# USB_Downloader.net
KiCad netlist of a schematic drawn in Altium Designer
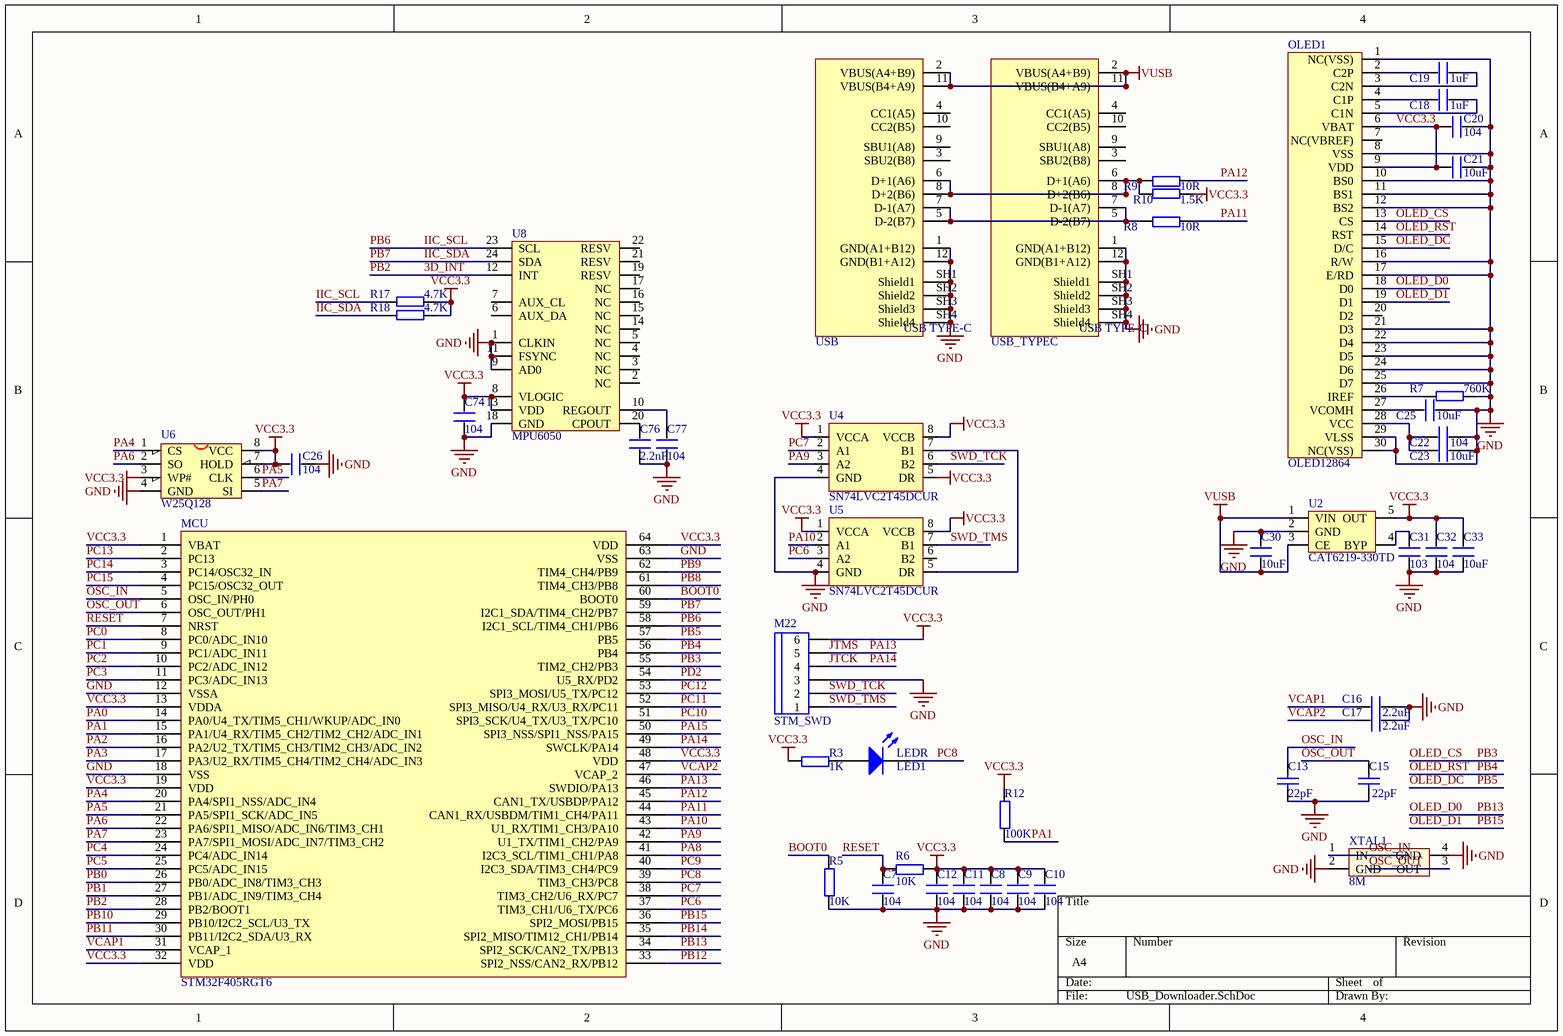
[diagram p0: USB_Downloader.SchDoc]

(export (version "E")
  (design (tool "Eeschema 10.0.6"))
  (components
    (comp (ref "C7")
      (value "104")
      (footprint "C 0603_L")
      (libsource (lib "WarShip V3 STM32103封装库") (part "C"))
    )
    (comp (ref "C8")
      (value "104")
      (footprint "C 0603_L")
      (libsource (lib "WarShip V3 STM32103封装库") (part "C"))
    )
    (comp (ref "C9")
      (value "104")
      (footprint "C 0603_L")
      (libsource (lib "WarShip V3 STM32103封装库") (part "C"))
    )
    (comp (ref "C10")
      (value "104")
      (footprint "C 0603_L")
      (libsource (lib "WarShip V3 STM32103封装库") (part "C"))
    )
    (comp (ref "C11")
      (value "104")
      (footprint "C 0603_L")
      (libsource (lib "WarShip V3 STM32103封装库") (part "C"))
    )
    (comp (ref "C12")
      (value "104")
      (footprint "C 0603_L")
      (libsource (lib "WarShip V3 STM32103封装库") (part "C"))
    )
    (comp (ref "C13") (value "22pF") (footprint "C 0603_L") (libsource (lib "L476") (part "CAP")))
    (comp (ref "C15") (value "22pF") (footprint "C 0603_L") (libsource (lib "L476") (part "CAP")))
    (comp (ref "C16")
      (value "2.2uF")
      (footprint "C 0603_L")
      (libsource (lib "WarShip V3 STM32103封装库") (part "C"))
    )
    (comp (ref "C17")
      (value "2.2uF")
      (footprint "C 0603_L")
      (libsource (lib "WarShip V3 STM32103封装库") (part "C"))
    )
    (comp (ref "C18")
      (value "1uF")
      (footprint "C 0603_L")
      (libsource (lib "WarShip V3 STM32103封装库") (part "C"))
    )
    (comp (ref "C19")
      (value "1uF")
      (footprint "C 0603_L")
      (libsource (lib "WarShip V3 STM32103封装库") (part "C"))
    )
    (comp (ref "C20")
      (value "104")
      (footprint "C 0603_L")
      (libsource (lib "WarShip V3 STM32103封装库") (part "C"))
    )
    (comp (ref "C21")
      (value "10uF")
      (footprint "C 0603_L")
      (libsource (lib "WarShip V3 STM32103封装库") (part "C"))
    )
    (comp (ref "C22")
      (value "104")
      (footprint "C 0603_L")
      (libsource (lib "WarShip V3 STM32103封装库") (part "C"))
    )
    (comp (ref "C23")
      (value "10uF")
      (footprint "C 0603_L")
      (libsource (lib "WarShip V3 STM32103封装库") (part "C"))
    )
    (comp (ref "C25")
      (value "10uF")
      (footprint "C 0603_L")
      (libsource (lib "WarShip V3 STM32103封装库") (part "C"))
    )
    (comp (ref "C26")
      (value "104")
      (footprint "C 0603_L")
      (libsource (lib "WarShip V3 STM32103封装库") (part "C"))
    )
    (comp (ref "C30")
      (value "10uF")
      (footprint "C 0603_L")
      (libsource (lib "WarShip V3 STM32103封装库") (part "C"))
    )
    (comp (ref "C31")
      (value "103")
      (footprint "C 0603_L")
      (libsource (lib "WarShip V3 STM32103封装库") (part "C"))
    )
    (comp (ref "C32")
      (value "104")
      (footprint "C 0603_L")
      (libsource (lib "WarShip V3 STM32103封装库") (part "C"))
    )
    (comp (ref "C33")
      (value "10uF")
      (footprint "C 0603_L")
      (libsource (lib "WarShip V3 STM32103封装库") (part "C"))
    )
    (comp (ref "C74") (value "104") (footprint "C 0603_L") (libsource (lib "MYCOMLIB") (part "C")))
    (comp (ref "C76") (value "2.2nF") (footprint "C 0603_L") (libsource (lib "MYCOMLIB") (part "C")))
    (comp (ref "C77") (value "104") (footprint "C 0603_L") (libsource (lib "MYCOMLIB") (part "C")))
    (comp (ref "LEDR")
      (value "LED1")
      (footprint "LED 0805B")
      (description "Typical RED, GREEN, YELLOW, AMBER GaAs LED")
      (fields (field (name "PUBLISHER") "Altium Limited"))
      (libsource (lib "阿波罗STM32F4&F7底板封装库") (part "LED2"))
    )
    (comp (ref "M22") (value "STM_SWD") (footprint "SH1.0-6P") (libsource (lib "MiniFly ") (part "HEAD6")))
    (comp (ref "MCU")
      (value "STM32F405RGT6")
      (footprint "LQFP64 10X10_L")
      (description "Flaah:256/RAM:48/IO:51")
      (libsource (lib "ATKF405 V1.1") (part "STM32F405RGT6"))
    )
    (comp (ref "OLED1")
      (value "OLED12864")
      (footprint "OLED_0.96")
      (libsource (lib "OLED模块封装库") (part "OLED12864"))
    )
    (comp (ref "R3")
      (value "1K")
      (footprint "R 0603_L")
      (libsource (lib "WarShip V3 STM32103封装库") (part "R"))
    )
    (comp (ref "R5")
      (value "10K")
      (footprint "R 0603_L")
      (libsource (lib "WarShip V3 STM32103封装库") (part "R"))
    )
    (comp (ref "R6")
      (value "10K")
      (footprint "R 0603_L")
      (libsource (lib "WarShip V3 STM32103封装库") (part "R"))
    )
    (comp (ref "R7")
      (value "760K")
      (footprint "R 0603_L")
      (libsource (lib "WarShip V3 STM32103封装库") (part "R"))
    )
    (comp (ref "R8")
      (value "10R")
      (footprint "R 0603_L")
      (libsource (lib "WarShip V3 STM32103封装库") (part "R"))
    )
    (comp (ref "R9")
      (value "10R")
      (footprint "R 0603_L")
      (libsource (lib "WarShip V3 STM32103封装库") (part "R"))
    )
    (comp (ref "R10")
      (value "1.5K")
      (footprint "R 0603_L")
      (libsource (lib "WarShip V3 STM32103封装库") (part "R"))
    )
    (comp (ref "R12")
      (value "100K")
      (footprint "R 0603_L")
      (libsource (lib "WarShip V3 STM32103封装库") (part "R"))
    )
    (comp (ref "R17")
      (value "4.7K")
      (footprint "R 0603_L")
      (libsource (lib "WarShip V3 STM32103封装库") (part "R"))
    )
    (comp (ref "R18")
      (value "4.7K")
      (footprint "R 0603_L")
      (libsource (lib "WarShip V3 STM32103封装库") (part "R"))
    )
    (comp (ref "U2")
      (value "CAT6219-330TD")
      (footprint "SOT23-5L")
      (description "3.3V 500mA LDO")
      (libsource (lib "STM32H743核心板封装库") (part "CAT6219-330TD"))
    )
    (comp (ref "U4")
      (value "SN74LVC2T45DCUR")
      (footprint "SN74LVC2T45DCUR")
      (description "双位双电源总线收发器")
      (libsource (lib "LovelessingSch") (part "SN74LVC2T45DCUR"))
    )
    (comp (ref "U5")
      (value "SN74LVC2T45DCUR")
      (footprint "SN74LVC2T45DCUR")
      (description "双位双电源总线收发器")
      (libsource (lib "LovelessingSch") (part "SN74LVC2T45DCUR"))
    )
    (comp (ref "U6")
      (value "W25Q128")
      (footprint "SOP8W_L")
      (description "W25X16;SST25VF016;MX25L1605")
      (libsource (lib "WarShip V3 STM32103封装库") (part "W25X16"))
    )
    (comp (ref "U8")
      (value "MPU6050")
      (footprint "QFN24 4x4_N")
      (description "9轴运动处理传感器")
      (libsource (lib "ALIENTEK_COMPONENT") (part "MPU6050"))
    )
    (comp (ref "USB")
      (value "USB TypeC")
      (footprint "USB Type-C")
      (description "12P TypeC 母座")
      (libsource (lib "ESP32_Weather") (part "USB Type-C"))
    )
    (comp (ref "USB_TYPEC")
      (value "USB TypeC")
      (footprint "USB Type-C")
      (description "12P TypeC 母座")
      (libsource (lib "ESP32_Weather") (part "USB Type-C"))
    )
    (comp (ref "XTAL1")
      (value "8M")
      (footprint "XTAL3225   无源")
      (description "无源贴片晶振")
      (libsource (lib "REMOTOR") (part "XTAL-无源贴片"))
    )
  )
  (nets
    (net (code "1") (name "/3D_INT") (class "Default")
      (node (ref "MCU") (pin "28") (pinfunction "PB2/BOOT1_28") (pintype "passive"))
      (node (ref "U8") (pin "12") (pinfunction "INT_12") (pintype "passive"))
    )
    (net (code "2") (name "/BOOT0") (class "Default")
      (node (ref "MCU") (pin "60") (pinfunction "BOOT0_60") (pintype "passive"))
      (node (ref "R5") (pin "2") (pintype "passive"))
    )
    (net (code "3") (name "/IIC_SCL") (class "Default")
      (node (ref "MCU") (pin "58") (pinfunction "I2C1_SCL/TIM4_CH1/PB6_58") (pintype "passive"))
      (node (ref "R17") (pin "2") (pintype "passive"))
      (node (ref "U8") (pin "23") (pinfunction "SCL_23") (pintype "passive"))
    )
    (net (code "4") (name "/IIC_SDA") (class "Default")
      (node (ref "MCU") (pin "59") (pinfunction "I2C1_SDA/TIM4_CH2/PB7_59") (pintype "passive"))
      (node (ref "R18") (pin "2") (pintype "passive"))
      (node (ref "U8") (pin "24") (pinfunction "SDA_24") (pintype "passive"))
    )
    (net (code "5") (name "/JTCK") (class "Default")
      (node (ref "M22") (pin "4") (pinfunction "4_4") (pintype "passive"))
      (node (ref "MCU") (pin "49") (pinfunction "SWCLK/PA14_49") (pintype "passive"))
    )
    (net (code "6") (name "/JTMS") (class "Default")
      (node (ref "M22") (pin "5") (pinfunction "5_5") (pintype "passive"))
      (node (ref "MCU") (pin "46") (pinfunction "SWDIO/PA13_46") (pintype "passive"))
    )
    (net (code "7") (name "/OLED_CS") (class "Default")
      (node (ref "MCU") (pin "55") (pinfunction "TIM2_CH2/PB3_55") (pintype "passive"))
      (node (ref "OLED1") (pin "13") (pinfunction "CS_13") (pintype "passive"))
    )
    (net (code "8") (name "/OLED_D0") (class "Default")
      (node (ref "MCU") (pin "34") (pinfunction "SPI2_SCK/CAN2_TX/PB13_34") (pintype "passive"))
      (node (ref "OLED1") (pin "18") (pinfunction "D0_18") (pintype "passive"))
    )
    (net (code "9") (name "/OLED_D1") (class "Default")
      (node (ref "MCU") (pin "36") (pinfunction "SPI2_MOSI/PB15_36") (pintype "passive"))
      (node (ref "OLED1") (pin "19") (pinfunction "D1_19") (pintype "passive"))
    )
    (net (code "10") (name "/OLED_DC") (class "Default")
      (node (ref "MCU") (pin "57") (pinfunction "PB5_57") (pintype "passive"))
      (node (ref "OLED1") (pin "15") (pinfunction "D/C_15") (pintype "passive"))
    )
    (net (code "11") (name "/OLED_RST") (class "Default")
      (node (ref "MCU") (pin "56") (pinfunction "PB4_56") (pintype "passive"))
      (node (ref "OLED1") (pin "14") (pinfunction "RST_14") (pintype "passive"))
    )
    (net (code "12") (name "/OSC_IN") (class "Default")
      (node (ref "C13") (pin "2") (pinfunction "2_2") (pintype "passive"))
      (node (ref "MCU") (pin "5") (pinfunction "OSC_IN/PH0_5") (pintype "passive"))
      (node (ref "XTAL1") (pin "1") (pinfunction "IN_1") (pintype "passive"))
    )
    (net (code "13") (name "/OSC_OUT") (class "Default")
      (node (ref "C15") (pin "2") (pinfunction "2_2") (pintype "passive"))
      (node (ref "MCU") (pin "6") (pinfunction "OSC_OUT/PH1_6") (pintype "passive"))
      (node (ref "XTAL1") (pin "3") (pinfunction "OUT_3") (pintype "passive"))
    )
    (net (code "14") (name "/PA0") (class "Default")
      (node (ref "MCU") (pin "14") (pinfunction "PA0/U4_TX/TIM5_CH1/WKUP/ADC_IN0_14") (pintype "passive"))
    )
    (net (code "15") (name "/PA1") (class "Default")
      (node (ref "MCU") (pin "15") (pinfunction "PA1/U4_RX/TIM5_CH2/TIM2_CH2/ADC_IN1_15") (pintype "passive"))
      (node (ref "R12") (pin "1") (pintype "passive"))
    )
    (net (code "16") (name "/PA2") (class "Default")
      (node (ref "MCU") (pin "16") (pinfunction "PA2/U2_TX/TIM5_CH3/TIM2_CH3/ADC_IN2_16") (pintype "passive"))
    )
    (net (code "17") (name "/PA3") (class "Default")
      (node (ref "MCU") (pin "17") (pinfunction "PA3/U2_RX/TIM5_CH4/TIM2_CH4/ADC_IN3_17") (pintype "passive"))
    )
    (net (code "18") (name "/PA4") (class "Default")
      (node (ref "MCU") (pin "20") (pinfunction "PA4/SPI1_NSS/ADC_IN4_20") (pintype "passive"))
      (node (ref "U6") (pin "1") (pinfunction "CS_1") (pintype "passive"))
    )
    (net (code "19") (name "/PA5") (class "Default")
      (node (ref "MCU") (pin "21") (pinfunction "PA5/SPI1_SCK/ADC_IN5_21") (pintype "passive"))
      (node (ref "U6") (pin "6") (pinfunction "CLK_6") (pintype "passive"))
    )
    (net (code "20") (name "/PA6") (class "Default")
      (node (ref "MCU") (pin "22") (pinfunction "PA6/SPI1_MISO/ADC_IN6/TIM3_CH1_22") (pintype "passive"))
      (node (ref "U6") (pin "2") (pinfunction "SO_2") (pintype "passive"))
    )
    (net (code "21") (name "/PA7") (class "Default")
      (node (ref "MCU") (pin "23") (pinfunction "PA7/SPI1_MOSI/ADC_IN7/TIM3_CH2_23") (pintype "passive"))
      (node (ref "U6") (pin "5") (pinfunction "SI_5") (pintype "passive"))
    )
    (net (code "22") (name "/PA8") (class "Default")
      (node (ref "MCU") (pin "41") (pinfunction "I2C3_SCL/TIM1_CH1/PA8_41") (pintype "passive"))
    )
    (net (code "23") (name "/PA9") (class "Default")
      (node (ref "MCU") (pin "42") (pinfunction "U1_TX/TIM1_CH2/PA9_42") (pintype "passive"))
      (node (ref "U4") (pin "3") (pinfunction "A2_3") (pintype "passive"))
    )
    (net (code "24") (name "/PA10") (class "Default")
      (node (ref "MCU") (pin "43") (pinfunction "U1_RX/TIM1_CH3/PA10_43") (pintype "passive"))
      (node (ref "U5") (pin "2") (pinfunction "A1_2") (pintype "passive"))
    )
    (net (code "25") (name "/PA11") (class "Default")
      (node (ref "MCU") (pin "44") (pinfunction "CAN1_RX/USBDM/TIM1_CH4/PA11_44") (pintype "passive"))
      (node (ref "R8") (pin "2") (pintype "passive"))
    )
    (net (code "26") (name "/PA12") (class "Default")
      (node (ref "MCU") (pin "45") (pinfunction "CAN1_TX/USBDP/PA12_45") (pintype "passive"))
      (node (ref "R9") (pin "2") (pintype "passive"))
    )
    (net (code "27") (name "/PA15") (class "Default")
      (node (ref "MCU") (pin "50") (pinfunction "SPI3_NSS/SPI1_NSS/PA15_50") (pintype "passive"))
    )
    (net (code "28") (name "/PB0") (class "Default")
      (node (ref "MCU") (pin "26") (pinfunction "PB0/ADC_IN8/TIM3_CH3_26") (pintype "passive"))
    )
    (net (code "29") (name "/PB1") (class "Default")
      (node (ref "MCU") (pin "27") (pinfunction "PB1/ADC_IN9/TIM3_CH4_27") (pintype "passive"))
    )
    (net (code "30") (name "/PB8") (class "Default")
      (node (ref "MCU") (pin "61") (pinfunction "TIM4_CH3/PB8_61") (pintype "passive"))
    )
    (net (code "31") (name "/PB9") (class "Default")
      (node (ref "MCU") (pin "62") (pinfunction "TIM4_CH4/PB9_62") (pintype "passive"))
    )
    (net (code "32") (name "/PB10") (class "Default")
      (node (ref "MCU") (pin "29") (pinfunction "PB10/I2C2_SCL/U3_TX_29") (pintype "passive"))
    )
    (net (code "33") (name "/PB11") (class "Default")
      (node (ref "MCU") (pin "30") (pinfunction "PB11/I2C2_SDA/U3_RX_30") (pintype "passive"))
    )
    (net (code "34") (name "/PB12") (class "Default")
      (node (ref "MCU") (pin "33") (pinfunction "SPI2_NSS/CAN2_RX/PB12_33") (pintype "passive"))
    )
    (net (code "35") (name "/PB14") (class "Default")
      (node (ref "MCU") (pin "35") (pinfunction "SPI2_MISO/TIM12_CH1/PB14_35") (pintype "passive"))
    )
    (net (code "36") (name "/PC0") (class "Default")
      (node (ref "MCU") (pin "8") (pinfunction "PC0/ADC_IN10_8") (pintype "passive"))
    )
    (net (code "37") (name "/PC1") (class "Default")
      (node (ref "MCU") (pin "9") (pinfunction "PC1/ADC_IN11_9") (pintype "passive"))
    )
    (net (code "38") (name "/PC2") (class "Default")
      (node (ref "MCU") (pin "10") (pinfunction "PC2/ADC_IN12_10") (pintype "passive"))
    )
    (net (code "39") (name "/PC3") (class "Default")
      (node (ref "MCU") (pin "11") (pinfunction "PC3/ADC_IN13_11") (pintype "passive"))
    )
    (net (code "40") (name "/PC4") (class "Default")
      (node (ref "MCU") (pin "24") (pinfunction "PC4/ADC_IN14_24") (pintype "passive"))
    )
    (net (code "41") (name "/PC5") (class "Default")
      (node (ref "MCU") (pin "25") (pinfunction "PC5/ADC_IN15_25") (pintype "passive"))
    )
    (net (code "42") (name "/PC6") (class "Default")
      (node (ref "MCU") (pin "37") (pinfunction "TIM3_CH1/U6_TX/PC6_37") (pintype "passive"))
      (node (ref "U5") (pin "3") (pinfunction "A2_3") (pintype "passive"))
    )
    (net (code "43") (name "/PC7") (class "Default")
      (node (ref "MCU") (pin "38") (pinfunction "TIM3_CH2/U6_RX/PC7_38") (pintype "passive"))
      (node (ref "U4") (pin "2") (pinfunction "A1_2") (pintype "passive"))
    )
    (net (code "44") (name "/PC8") (class "Default")
      (node (ref "LEDR") (pin "2") (pinfunction "K_2") (pintype "passive"))
      (node (ref "MCU") (pin "39") (pinfunction "TIM3_CH3/PC8_39") (pintype "passive"))
    )
    (net (code "45") (name "/PC9") (class "Default")
      (node (ref "MCU") (pin "40") (pinfunction "I2C3_SDA/TIM3_CH4/PC9_40") (pintype "passive"))
    )
    (net (code "46") (name "/PC10") (class "Default")
      (node (ref "MCU") (pin "51") (pinfunction "SPI3_SCK/U4_TX/U3_TX/PC10_51") (pintype "passive"))
    )
    (net (code "47") (name "/PC11") (class "Default")
      (node (ref "MCU") (pin "52") (pinfunction "SPI3_MISO/U4_RX/U3_RX/PC11_52") (pintype "passive"))
    )
    (net (code "48") (name "/PC12") (class "Default")
      (node (ref "MCU") (pin "53") (pinfunction "SPI3_MOSI/U5_TX/PC12_53") (pintype "passive"))
    )
    (net (code "49") (name "/PC13") (class "Default")
      (node (ref "MCU") (pin "2") (pinfunction "PC13_2") (pintype "passive"))
    )
    (net (code "50") (name "/PC14") (class "Default")
      (node (ref "MCU") (pin "3") (pinfunction "PC14/OSC32_IN_3") (pintype "passive"))
    )
    (net (code "51") (name "/PC15") (class "Default")
      (node (ref "MCU") (pin "4") (pinfunction "PC15/OSC32_OUT_4") (pintype "passive"))
    )
    (net (code "52") (name "/PD2") (class "Default")
      (node (ref "MCU") (pin "54") (pinfunction "U5_RX/PD2_54") (pintype "passive"))
    )
    (net (code "53") (name "/RESET") (class "Default")
      (node (ref "C7") (pin "2") (pintype "passive"))
      (node (ref "MCU") (pin "7") (pinfunction "NRST_7") (pintype "passive"))
      (node (ref "R6") (pin "1") (pintype "passive"))
    )
    (net (code "54") (name "/SWD_TCK") (class "Default")
      (node (ref "M22") (pin "2") (pinfunction "2_2") (pintype "passive"))
      (node (ref "U4") (pin "6") (pinfunction "B2_6") (pintype "passive"))
    )
    (net (code "55") (name "/SWD_TMS") (class "Default")
      (node (ref "M22") (pin "1") (pinfunction "1_1") (pintype "passive"))
      (node (ref "U5") (pin "7") (pinfunction "B1_7") (pintype "passive"))
    )
    (net (code "56") (name "/VCAP1") (class "Default")
      (node (ref "C16") (pin "2") (pintype "passive"))
      (node (ref "MCU") (pin "31") (pinfunction "VCAP_1_31") (pintype "passive"))
    )
    (net (code "57") (name "/VCAP2") (class "Default")
      (node (ref "C17") (pin "2") (pintype "passive"))
      (node (ref "MCU") (pin "47") (pinfunction "VCAP_2_47") (pintype "passive"))
    )
    (net (code "58") (name "GND") (class "Default")
      (node (ref "C10") (pin "1") (pintype "passive"))
      (node (ref "C11") (pin "1") (pintype "passive"))
      (node (ref "C12") (pin "1") (pintype "passive"))
      (node (ref "C13") (pin "1") (pinfunction "1_1") (pintype "passive"))
      (node (ref "C15") (pin "1") (pinfunction "1_1") (pintype "passive"))
      (node (ref "C16") (pin "1") (pintype "passive"))
      (node (ref "C17") (pin "1") (pintype "passive"))
      (node (ref "C20") (pin "1") (pintype "passive"))
      (node (ref "C21") (pin "1") (pintype "passive"))
      (node (ref "C22") (pin "1") (pintype "passive"))
      (node (ref "C23") (pin "1") (pintype "passive"))
      (node (ref "C25") (pin "1") (pintype "passive"))
      (node (ref "C26") (pin "2") (pintype "passive"))
      (node (ref "C30") (pin "2") (pintype "passive"))
      (node (ref "C31") (pin "1") (pintype "passive"))
      (node (ref "C32") (pin "1") (pintype "passive"))
      (node (ref "C33") (pin "1") (pintype "passive"))
      (node (ref "C7") (pin "1") (pintype "passive"))
      (node (ref "C74") (pin "1") (pintype "passive"))
      (node (ref "C76") (pin "1") (pintype "passive"))
      (node (ref "C77") (pin "2") (pintype "passive"))
      (node (ref "C8") (pin "1") (pintype "passive"))
      (node (ref "C9") (pin "1") (pintype "passive"))
      (node (ref "M22") (pin "3") (pinfunction "3_3") (pintype "passive"))
      (node (ref "MCU") (pin "12") (pinfunction "VSSA_12") (pintype "passive"))
      (node (ref "MCU") (pin "18") (pinfunction "VSS_18") (pintype "passive"))
      (node (ref "MCU") (pin "63") (pinfunction "VSS_63") (pintype "passive"))
      (node (ref "OLED1") (pin "1") (pinfunction "NC(VSS)_1") (pintype "passive"))
      (node (ref "OLED1") (pin "10") (pinfunction "BS0_10") (pintype "passive"))
      (node (ref "OLED1") (pin "11") (pinfunction "BS1_11") (pintype "passive"))
      (node (ref "OLED1") (pin "12") (pinfunction "BS2_12") (pintype "passive"))
      (node (ref "OLED1") (pin "16") (pinfunction "R/W_16") (pintype "passive"))
      (node (ref "OLED1") (pin "17") (pinfunction "E/RD_17") (pintype "passive"))
      (node (ref "OLED1") (pin "21") (pinfunction "D3_21") (pintype "passive"))
      (node (ref "OLED1") (pin "22") (pinfunction "D4_22") (pintype "passive"))
      (node (ref "OLED1") (pin "23") (pinfunction "D5_23") (pintype "passive"))
      (node (ref "OLED1") (pin "24") (pinfunction "D6_24") (pintype "passive"))
      (node (ref "OLED1") (pin "25") (pinfunction "D7_25") (pintype "passive"))
      (node (ref "OLED1") (pin "29") (pinfunction "VLSS_29") (pintype "passive"))
      (node (ref "OLED1") (pin "30") (pinfunction "NC(VSS)_30") (pintype "passive"))
      (node (ref "OLED1") (pin "8") (pinfunction "VSS_8") (pintype "passive"))
      (node (ref "R5") (pin "1") (pintype "passive"))
      (node (ref "R7") (pin "1") (pintype "passive"))
      (node (ref "U2") (pin "2") (pinfunction "GND_2") (pintype "passive"))
      (node (ref "U4") (pin "4") (pinfunction "GND_4") (pintype "passive"))
      (node (ref "U5") (pin "4") (pinfunction "GND_4") (pintype "passive"))
      (node (ref "U6") (pin "4") (pinfunction "GND_4") (pintype "passive"))
      (node (ref "U8") (pin "1") (pinfunction "CLKIN_1") (pintype "passive"))
      (node (ref "U8") (pin "11") (pinfunction "FSYNC_11") (pintype "passive"))
      (node (ref "U8") (pin "18") (pinfunction "GND_18") (pintype "passive"))
      (node (ref "U8") (pin "9") (pinfunction "AD0_9") (pintype "passive"))
      (node (ref "USB") (pin "1") (pinfunction "GND(A1+B12)_1") (pintype "passive"))
      (node (ref "USB") (pin "12") (pinfunction "GND(B1+A12)_12") (pintype "passive"))
      (node (ref "USB") (pin "SH1") (pinfunction "Shield1_SH1") (pintype "passive"))
      (node (ref "USB") (pin "SH2") (pinfunction "Shield2_SH2") (pintype "passive"))
      (node (ref "USB") (pin "SH3") (pinfunction "Shield3_SH3") (pintype "passive"))
      (node (ref "USB") (pin "SH4") (pinfunction "Shield4_SH4") (pintype "passive"))
      (node (ref "USB_TYPEC") (pin "1") (pinfunction "GND(A1+B12)_1") (pintype "passive"))
      (node (ref "USB_TYPEC") (pin "12") (pinfunction "GND(B1+A12)_12") (pintype "passive"))
      (node (ref "USB_TYPEC") (pin "SH1") (pinfunction "Shield1_SH1") (pintype "passive"))
      (node (ref "USB_TYPEC") (pin "SH2") (pinfunction "Shield2_SH2") (pintype "passive"))
      (node (ref "USB_TYPEC") (pin "SH3") (pinfunction "Shield3_SH3") (pintype "passive"))
      (node (ref "USB_TYPEC") (pin "SH4") (pinfunction "Shield4_SH4") (pintype "passive"))
      (node (ref "XTAL1") (pin "2") (pinfunction "GND_2") (pintype "passive"))
      (node (ref "XTAL1") (pin "4") (pinfunction "GND_4") (pintype "passive"))
    )
    (net (code "59") (name "Net-(LEDR-A)") (class "Default")
      (node (ref "LEDR") (pin "1") (pinfunction "A_1") (pintype "passive"))
      (node (ref "R3") (pin "2") (pintype "passive"))
    )
    (net (code "60") (name "Net-(OLED1-C1N)") (class "Default")
      (node (ref "C18") (pin "1") (pintype "passive"))
      (node (ref "OLED1") (pin "5") (pinfunction "C1N_5") (pintype "passive"))
    )
    (net (code "61") (name "Net-(OLED1-C1P)") (class "Default")
      (node (ref "C18") (pin "2") (pintype "passive"))
      (node (ref "OLED1") (pin "4") (pinfunction "C1P_4") (pintype "passive"))
    )
    (net (code "62") (name "Net-(OLED1-C2N)") (class "Default")
      (node (ref "C19") (pin "1") (pintype "passive"))
      (node (ref "OLED1") (pin "3") (pinfunction "C2N_3") (pintype "passive"))
    )
    (net (code "63") (name "Net-(OLED1-C2P)") (class "Default")
      (node (ref "C19") (pin "2") (pintype "passive"))
      (node (ref "OLED1") (pin "2") (pinfunction "C2P_2") (pintype "passive"))
    )
    (net (code "64") (name "Net-(OLED1-IREF)") (class "Default")
      (node (ref "OLED1") (pin "26") (pinfunction "IREF_26") (pintype "passive"))
      (node (ref "R7") (pin "2") (pintype "passive"))
    )
    (net (code "65") (name "Net-(OLED1-VCC)") (class "Default")
      (node (ref "C22") (pin "2") (pintype "passive"))
      (node (ref "C23") (pin "2") (pintype "passive"))
      (node (ref "OLED1") (pin "28") (pinfunction "VCC_28") (pintype "passive"))
    )
    (net (code "66") (name "Net-(OLED1-VCOMH)") (class "Default")
      (node (ref "C25") (pin "2") (pintype "passive"))
      (node (ref "OLED1") (pin "27") (pinfunction "VCOMH_27") (pintype "passive"))
    )
    (net (code "67") (name "Net-(U2-BYP)") (class "Default")
      (node (ref "C31") (pin "2") (pintype "passive"))
      (node (ref "U2") (pin "4") (pinfunction "BYP_4") (pintype "passive"))
    )
    (net (code "68") (name "Net-(U4-B1)") (class "Default")
      (node (ref "U4") (pin "7") (pinfunction "B1_7") (pintype "passive"))
      (node (ref "U5") (pin "5") (pinfunction "DR_5") (pintype "passive"))
    )
    (net (code "69") (name "Net-(U8-CPOUT)") (class "Default")
      (node (ref "C76") (pin "2") (pintype "passive"))
      (node (ref "U8") (pin "20") (pinfunction "CPOUT_20") (pintype "passive"))
    )
    (net (code "70") (name "Net-(U8-REGOUT)") (class "Default")
      (node (ref "C77") (pin "1") (pintype "passive"))
      (node (ref "U8") (pin "10") (pinfunction "REGOUT_10") (pintype "passive"))
    )
    (net (code "71") (name "Net-(USB-D+1(A6))") (class "Default")
      (node (ref "R10") (pin "2") (pintype "passive"))
      (node (ref "R9") (pin "1") (pintype "passive"))
      (node (ref "USB") (pin "6") (pinfunction "D+1(A6)_6") (pintype "passive"))
      (node (ref "USB") (pin "8") (pinfunction "D+2(B6)_8") (pintype "passive"))
      (node (ref "USB_TYPEC") (pin "6") (pinfunction "D+1(A6)_6") (pintype "passive"))
      (node (ref "USB_TYPEC") (pin "8") (pinfunction "D+2(B6)_8") (pintype "passive"))
    )
    (net (code "72") (name "Net-(USB-D-1(A7))") (class "Default")
      (node (ref "R8") (pin "1") (pintype "passive"))
      (node (ref "USB") (pin "5") (pinfunction "D-2(B7)_5") (pintype "passive"))
      (node (ref "USB") (pin "7") (pinfunction "D-1(A7)_7") (pintype "passive"))
      (node (ref "USB_TYPEC") (pin "5") (pinfunction "D-2(B7)_5") (pintype "passive"))
      (node (ref "USB_TYPEC") (pin "7") (pinfunction "D-1(A7)_7") (pintype "passive"))
    )
    (net (code "73") (name "VCC3.3") (class "Default")
      (node (ref "C10") (pin "2") (pintype "passive"))
      (node (ref "C11") (pin "2") (pintype "passive"))
      (node (ref "C12") (pin "2") (pintype "passive"))
      (node (ref "C20") (pin "2") (pintype "passive"))
      (node (ref "C21") (pin "2") (pintype "passive"))
      (node (ref "C26") (pin "1") (pintype "passive"))
      (node (ref "C32") (pin "2") (pintype "passive"))
      (node (ref "C33") (pin "2") (pintype "passive"))
      (node (ref "C74") (pin "2") (pintype "passive"))
      (node (ref "C8") (pin "2") (pintype "passive"))
      (node (ref "C9") (pin "2") (pintype "passive"))
      (node (ref "M22") (pin "6") (pinfunction "6_6") (pintype "passive"))
      (node (ref "MCU") (pin "1") (pinfunction "VBAT_1") (pintype "passive"))
      (node (ref "MCU") (pin "13") (pinfunction "VDDA_13") (pintype "passive"))
      (node (ref "MCU") (pin "19") (pinfunction "VDD_19") (pintype "passive"))
      (node (ref "MCU") (pin "32") (pinfunction "VDD_32") (pintype "passive"))
      (node (ref "MCU") (pin "48") (pinfunction "VDD_48") (pintype "passive"))
      (node (ref "MCU") (pin "64") (pinfunction "VDD_64") (pintype "passive"))
      (node (ref "OLED1") (pin "6") (pinfunction "VBAT_6") (pintype "passive"))
      (node (ref "OLED1") (pin "9") (pinfunction "VDD_9") (pintype "passive"))
      (node (ref "R10") (pin "1") (pintype "passive"))
      (node (ref "R12") (pin "2") (pintype "passive"))
      (node (ref "R17") (pin "1") (pintype "passive"))
      (node (ref "R18") (pin "1") (pintype "passive"))
      (node (ref "R3") (pin "1") (pintype "passive"))
      (node (ref "R6") (pin "2") (pintype "passive"))
      (node (ref "U2") (pin "5") (pinfunction "OUT_5") (pintype "passive"))
      (node (ref "U4") (pin "1") (pinfunction "VCCA_1") (pintype "passive"))
      (node (ref "U4") (pin "5") (pinfunction "DR_5") (pintype "passive"))
      (node (ref "U4") (pin "8") (pinfunction "VCCB_8") (pintype "passive"))
      (node (ref "U5") (pin "1") (pinfunction "VCCA_1") (pintype "passive"))
      (node (ref "U5") (pin "8") (pinfunction "VCCB_8") (pintype "passive"))
      (node (ref "U6") (pin "3") (pinfunction "WP#_3") (pintype "passive"))
      (node (ref "U6") (pin "7") (pinfunction "HOLD_7") (pintype "passive"))
      (node (ref "U6") (pin "8") (pinfunction "VCC_8") (pintype "passive"))
      (node (ref "U8") (pin "13") (pinfunction "VDD_13") (pintype "passive"))
      (node (ref "U8") (pin "8") (pinfunction "VLOGIC_8") (pintype "passive"))
    )
    (net (code "74") (name "VUSB") (class "Default")
      (node (ref "C30") (pin "1") (pintype "passive"))
      (node (ref "U2") (pin "1") (pinfunction "VIN_1") (pintype "passive"))
      (node (ref "U2") (pin "3") (pinfunction "CE_3") (pintype "passive"))
      (node (ref "USB") (pin "11") (pinfunction "VBUS(B4+A9)_11") (pintype "passive"))
      (node (ref "USB") (pin "2") (pinfunction "VBUS(A4+B9)_2") (pintype "passive"))
      (node (ref "USB_TYPEC") (pin "11") (pinfunction "VBUS(B4+A9)_11") (pintype "passive"))
      (node (ref "USB_TYPEC") (pin "2") (pinfunction "VBUS(A4+B9)_2") (pintype "passive"))
    )
    (net (code "75") (name "unconnected-(OLED1-D2-Pad20)") (class "Default")
      (node (ref "OLED1") (pin "20") (pinfunction "D2_20") (pintype "passive"))
    )
    (net (code "76") (name "unconnected-(OLED1-NC(VBREF)-Pad7)") (class "Default")
      (node (ref "OLED1") (pin "7") (pinfunction "NC(VBREF)_7") (pintype "passive"))
    )
    (net (code "77") (name "unconnected-(U5-B2-Pad6)") (class "Default")
      (node (ref "U5") (pin "6") (pinfunction "B2_6") (pintype "passive"))
    )
    (net (code "78") (name "unconnected-(U8-AUX_CL-Pad7)") (class "Default")
      (node (ref "U8") (pin "7") (pinfunction "AUX_CL_7") (pintype "passive"))
    )
    (net (code "79") (name "unconnected-(U8-AUX_DA-Pad6)") (class "Default")
      (node (ref "U8") (pin "6") (pinfunction "AUX_DA_6") (pintype "passive"))
    )
    (net (code "80") (name "unconnected-(U8-NC-Pad2)") (class "Default")
      (node (ref "U8") (pin "2") (pinfunction "NC_2") (pintype "passive"))
    )
    (net (code "81") (name "unconnected-(U8-NC-Pad3)") (class "Default")
      (node (ref "U8") (pin "3") (pinfunction "NC_3") (pintype "passive"))
    )
    (net (code "82") (name "unconnected-(U8-NC-Pad4)") (class "Default")
      (node (ref "U8") (pin "4") (pinfunction "NC_4") (pintype "passive"))
    )
    (net (code "83") (name "unconnected-(U8-NC-Pad5)") (class "Default")
      (node (ref "U8") (pin "5") (pinfunction "NC_5") (pintype "passive"))
    )
    (net (code "84") (name "unconnected-(U8-NC-Pad14)") (class "Default")
      (node (ref "U8") (pin "14") (pinfunction "NC_14") (pintype "passive"))
    )
    (net (code "85") (name "unconnected-(U8-NC-Pad15)") (class "Default")
      (node (ref "U8") (pin "15") (pinfunction "NC_15") (pintype "passive"))
    )
    (net (code "86") (name "unconnected-(U8-NC-Pad16)") (class "Default")
      (node (ref "U8") (pin "16") (pinfunction "NC_16") (pintype "passive"))
    )
    (net (code "87") (name "unconnected-(U8-NC-Pad17)") (class "Default")
      (node (ref "U8") (pin "17") (pinfunction "NC_17") (pintype "passive"))
    )
    (net (code "88") (name "unconnected-(U8-RESV-Pad19)") (class "Default")
      (node (ref "U8") (pin "19") (pinfunction "RESV_19") (pintype "passive"))
    )
    (net (code "89") (name "unconnected-(U8-RESV-Pad21)") (class "Default")
      (node (ref "U8") (pin "21") (pinfunction "RESV_21") (pintype "passive"))
    )
    (net (code "90") (name "unconnected-(U8-RESV-Pad22)") (class "Default")
      (node (ref "U8") (pin "22") (pinfunction "RESV_22") (pintype "passive"))
    )
    (net (code "91") (name "unconnected-(USB-CC1(A5)-Pad4)") (class "Default")
      (node (ref "USB") (pin "4") (pinfunction "CC1(A5)_4") (pintype "passive"))
    )
    (net (code "92") (name "unconnected-(USB-CC2(B5)-Pad10)") (class "Default")
      (node (ref "USB") (pin "10") (pinfunction "CC2(B5)_10") (pintype "passive"))
    )
    (net (code "93") (name "unconnected-(USB-SBU1(A8)-Pad9)") (class "Default")
      (node (ref "USB") (pin "9") (pinfunction "SBU1(A8)_9") (pintype "passive"))
    )
    (net (code "94") (name "unconnected-(USB-SBU2(B8)-Pad3)") (class "Default")
      (node (ref "USB") (pin "3") (pinfunction "SBU2(B8)_3") (pintype "passive"))
    )
    (net (code "95") (name "unconnected-(USB_TYPEC-CC1(A5)-Pad4)") (class "Default")
      (node (ref "USB_TYPEC") (pin "4") (pinfunction "CC1(A5)_4") (pintype "passive"))
    )
    (net (code "96") (name "unconnected-(USB_TYPEC-CC2(B5)-Pad10)") (class "Default")
      (node (ref "USB_TYPEC") (pin "10") (pinfunction "CC2(B5)_10") (pintype "passive"))
    )
    (net (code "97") (name "unconnected-(USB_TYPEC-SBU1(A8)-Pad9)") (class "Default")
      (node (ref "USB_TYPEC") (pin "9") (pinfunction "SBU1(A8)_9") (pintype "passive"))
    )
    (net (code "98") (name "unconnected-(USB_TYPEC-SBU2(B8)-Pad3)") (class "Default")
      (node (ref "USB_TYPEC") (pin "3") (pinfunction "SBU2(B8)_3") (pintype "passive"))
    )
  )
)
